# LED_String_QBHP686.net
KiCad netlist of a schematic drawn in Altium Designer
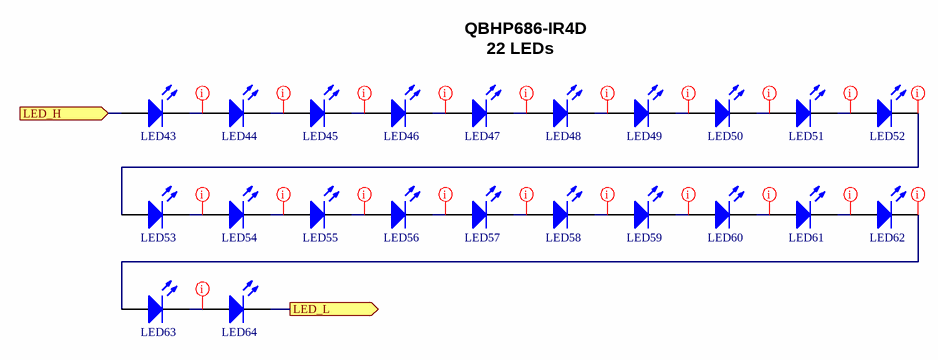
[diagram p0: LED_String_QBHP686.SchDoc]

(export (version "E")
  (design (tool "Eeschema 10.0.6"))
  (components
    (comp (ref "LED43")
      (value "QBHP686-IR4D")
      (footprint "QBHP686-IR4D")
      (description "Infrared (IR) Emitter 740nm 1.8V 100mA 5.6mW/sr @ 50mA 120° 1411 (3528 Metric)")
      (fields (field (name "MFR") "QT Brightek (QTB)") (field (name "MANUFACTURER") "QT-Brightek"))
      (libsource (lib "ETHZ Vault") (part "LED"))
    )
    (comp (ref "LED44")
      (value "QBHP686-IR4D")
      (footprint "QBHP686-IR4D")
      (description "Infrared (IR) Emitter 740nm 1.8V 100mA 5.6mW/sr @ 50mA 120° 1411 (3528 Metric)")
      (fields (field (name "MFR") "QT Brightek (QTB)") (field (name "MANUFACTURER") "QT-Brightek"))
      (libsource (lib "ETHZ Vault") (part "LED"))
    )
    (comp (ref "LED45")
      (value "QBHP686-IR4D")
      (footprint "QBHP686-IR4D")
      (description "Infrared (IR) Emitter 740nm 1.8V 100mA 5.6mW/sr @ 50mA 120° 1411 (3528 Metric)")
      (fields (field (name "MFR") "QT Brightek (QTB)") (field (name "MANUFACTURER") "QT-Brightek"))
      (libsource (lib "ETHZ Vault") (part "LED"))
    )
    (comp (ref "LED46")
      (value "QBHP686-IR4D")
      (footprint "QBHP686-IR4D")
      (description "Infrared (IR) Emitter 740nm 1.8V 100mA 5.6mW/sr @ 50mA 120° 1411 (3528 Metric)")
      (fields (field (name "MFR") "QT Brightek (QTB)") (field (name "MANUFACTURER") "QT-Brightek"))
      (libsource (lib "ETHZ Vault") (part "LED"))
    )
    (comp (ref "LED47")
      (value "QBHP686-IR4D")
      (footprint "QBHP686-IR4D")
      (description "Infrared (IR) Emitter 740nm 1.8V 100mA 5.6mW/sr @ 50mA 120° 1411 (3528 Metric)")
      (fields (field (name "MFR") "QT Brightek (QTB)") (field (name "MANUFACTURER") "QT-Brightek"))
      (libsource (lib "ETHZ Vault") (part "LED"))
    )
    (comp (ref "LED48")
      (value "QBHP686-IR4D")
      (footprint "QBHP686-IR4D")
      (description "Infrared (IR) Emitter 740nm 1.8V 100mA 5.6mW/sr @ 50mA 120° 1411 (3528 Metric)")
      (fields (field (name "MFR") "QT Brightek (QTB)") (field (name "MANUFACTURER") "QT-Brightek"))
      (libsource (lib "ETHZ Vault") (part "LED"))
    )
    (comp (ref "LED49")
      (value "QBHP686-IR4D")
      (footprint "QBHP686-IR4D")
      (description "Infrared (IR) Emitter 740nm 1.8V 100mA 5.6mW/sr @ 50mA 120° 1411 (3528 Metric)")
      (fields (field (name "MFR") "QT Brightek (QTB)") (field (name "MANUFACTURER") "QT-Brightek"))
      (libsource (lib "ETHZ Vault") (part "LED"))
    )
    (comp (ref "LED50")
      (value "QBHP686-IR4D")
      (footprint "QBHP686-IR4D")
      (description "Infrared (IR) Emitter 740nm 1.8V 100mA 5.6mW/sr @ 50mA 120° 1411 (3528 Metric)")
      (fields (field (name "MFR") "QT Brightek (QTB)") (field (name "MANUFACTURER") "QT-Brightek"))
      (libsource (lib "ETHZ Vault") (part "LED"))
    )
    (comp (ref "LED51")
      (value "QBHP686-IR4D")
      (footprint "QBHP686-IR4D")
      (description "Infrared (IR) Emitter 740nm 1.8V 100mA 5.6mW/sr @ 50mA 120° 1411 (3528 Metric)")
      (fields (field (name "MFR") "QT Brightek (QTB)") (field (name "MANUFACTURER") "QT-Brightek"))
      (libsource (lib "ETHZ Vault") (part "LED"))
    )
    (comp (ref "LED52")
      (value "QBHP686-IR4D")
      (footprint "QBHP686-IR4D")
      (description "Infrared (IR) Emitter 740nm 1.8V 100mA 5.6mW/sr @ 50mA 120° 1411 (3528 Metric)")
      (fields (field (name "MFR") "QT Brightek (QTB)") (field (name "MANUFACTURER") "QT-Brightek"))
      (libsource (lib "ETHZ Vault") (part "LED"))
    )
    (comp (ref "LED53")
      (value "QBHP686-IR4D")
      (footprint "QBHP686-IR4D")
      (description "Infrared (IR) Emitter 740nm 1.8V 100mA 5.6mW/sr @ 50mA 120° 1411 (3528 Metric)")
      (fields (field (name "MFR") "QT Brightek (QTB)") (field (name "MANUFACTURER") "QT-Brightek"))
      (libsource (lib "ETHZ Vault") (part "LED"))
    )
    (comp (ref "LED54")
      (value "QBHP686-IR4D")
      (footprint "QBHP686-IR4D")
      (description "Infrared (IR) Emitter 740nm 1.8V 100mA 5.6mW/sr @ 50mA 120° 1411 (3528 Metric)")
      (fields (field (name "MFR") "QT Brightek (QTB)") (field (name "MANUFACTURER") "QT-Brightek"))
      (libsource (lib "ETHZ Vault") (part "LED"))
    )
    (comp (ref "LED55")
      (value "QBHP686-IR4D")
      (footprint "QBHP686-IR4D")
      (description "Infrared (IR) Emitter 740nm 1.8V 100mA 5.6mW/sr @ 50mA 120° 1411 (3528 Metric)")
      (fields (field (name "MFR") "QT Brightek (QTB)") (field (name "MANUFACTURER") "QT-Brightek"))
      (libsource (lib "ETHZ Vault") (part "LED"))
    )
    (comp (ref "LED56")
      (value "QBHP686-IR4D")
      (footprint "QBHP686-IR4D")
      (description "Infrared (IR) Emitter 740nm 1.8V 100mA 5.6mW/sr @ 50mA 120° 1411 (3528 Metric)")
      (fields (field (name "MFR") "QT Brightek (QTB)") (field (name "MANUFACTURER") "QT-Brightek"))
      (libsource (lib "ETHZ Vault") (part "LED"))
    )
    (comp (ref "LED57")
      (value "QBHP686-IR4D")
      (footprint "QBHP686-IR4D")
      (description "Infrared (IR) Emitter 740nm 1.8V 100mA 5.6mW/sr @ 50mA 120° 1411 (3528 Metric)")
      (fields (field (name "MFR") "QT Brightek (QTB)") (field (name "MANUFACTURER") "QT-Brightek"))
      (libsource (lib "ETHZ Vault") (part "LED"))
    )
    (comp (ref "LED58")
      (value "QBHP686-IR4D")
      (footprint "QBHP686-IR4D")
      (description "Infrared (IR) Emitter 740nm 1.8V 100mA 5.6mW/sr @ 50mA 120° 1411 (3528 Metric)")
      (fields (field (name "MFR") "QT Brightek (QTB)") (field (name "MANUFACTURER") "QT-Brightek"))
      (libsource (lib "ETHZ Vault") (part "LED"))
    )
    (comp (ref "LED59")
      (value "QBHP686-IR4D")
      (footprint "QBHP686-IR4D")
      (description "Infrared (IR) Emitter 740nm 1.8V 100mA 5.6mW/sr @ 50mA 120° 1411 (3528 Metric)")
      (fields (field (name "MFR") "QT Brightek (QTB)") (field (name "MANUFACTURER") "QT-Brightek"))
      (libsource (lib "ETHZ Vault") (part "LED"))
    )
    (comp (ref "LED60")
      (value "QBHP686-IR4D")
      (footprint "QBHP686-IR4D")
      (description "Infrared (IR) Emitter 740nm 1.8V 100mA 5.6mW/sr @ 50mA 120° 1411 (3528 Metric)")
      (fields (field (name "MFR") "QT Brightek (QTB)") (field (name "MANUFACTURER") "QT-Brightek"))
      (libsource (lib "ETHZ Vault") (part "LED"))
    )
    (comp (ref "LED61")
      (value "QBHP686-IR4D")
      (footprint "QBHP686-IR4D")
      (description "Infrared (IR) Emitter 740nm 1.8V 100mA 5.6mW/sr @ 50mA 120° 1411 (3528 Metric)")
      (fields (field (name "MFR") "QT Brightek (QTB)") (field (name "MANUFACTURER") "QT-Brightek"))
      (libsource (lib "ETHZ Vault") (part "LED"))
    )
    (comp (ref "LED62")
      (value "QBHP686-IR4D")
      (footprint "QBHP686-IR4D")
      (description "Infrared (IR) Emitter 740nm 1.8V 100mA 5.6mW/sr @ 50mA 120° 1411 (3528 Metric)")
      (fields (field (name "MFR") "QT Brightek (QTB)") (field (name "MANUFACTURER") "QT-Brightek"))
      (libsource (lib "ETHZ Vault") (part "LED"))
    )
    (comp (ref "LED63")
      (value "QBHP686-IR4D")
      (footprint "QBHP686-IR4D")
      (description "Infrared (IR) Emitter 740nm 1.8V 100mA 5.6mW/sr @ 50mA 120° 1411 (3528 Metric)")
      (fields (field (name "MFR") "QT Brightek (QTB)") (field (name "MANUFACTURER") "QT-Brightek"))
      (libsource (lib "ETHZ Vault") (part "LED"))
    )
    (comp (ref "LED64")
      (value "QBHP686-IR4D")
      (footprint "QBHP686-IR4D")
      (description "Infrared (IR) Emitter 740nm 1.8V 100mA 5.6mW/sr @ 50mA 120° 1411 (3528 Metric)")
      (fields (field (name "MFR") "QT Brightek (QTB)") (field (name "MANUFACTURER") "QT-Brightek"))
      (libsource (lib "ETHZ Vault") (part "LED"))
    )
  )
  (nets
    (net (code "1") (name "/LED_H") (class "Default")
      (node (ref "LED43") (pin "2") (pinfunction "A_2") (pintype "passive"))
    )
    (net (code "2") (name "/LED_L") (class "Default")
      (node (ref "LED64") (pin "1") (pinfunction "K_1") (pintype "passive"))
    )
    (net (code "3") (name "Net-(LED43-K)") (class "Default")
      (node (ref "LED43") (pin "1") (pinfunction "K_1") (pintype "passive"))
      (node (ref "LED44") (pin "2") (pinfunction "A_2") (pintype "passive"))
    )
    (net (code "4") (name "Net-(LED44-K)") (class "Default")
      (node (ref "LED44") (pin "1") (pinfunction "K_1") (pintype "passive"))
      (node (ref "LED45") (pin "2") (pinfunction "A_2") (pintype "passive"))
    )
    (net (code "5") (name "Net-(LED45-K)") (class "Default")
      (node (ref "LED45") (pin "1") (pinfunction "K_1") (pintype "passive"))
      (node (ref "LED46") (pin "2") (pinfunction "A_2") (pintype "passive"))
    )
    (net (code "6") (name "Net-(LED46-K)") (class "Default")
      (node (ref "LED46") (pin "1") (pinfunction "K_1") (pintype "passive"))
      (node (ref "LED47") (pin "2") (pinfunction "A_2") (pintype "passive"))
    )
    (net (code "7") (name "Net-(LED47-K)") (class "Default")
      (node (ref "LED47") (pin "1") (pinfunction "K_1") (pintype "passive"))
      (node (ref "LED48") (pin "2") (pinfunction "A_2") (pintype "passive"))
    )
    (net (code "8") (name "Net-(LED48-K)") (class "Default")
      (node (ref "LED48") (pin "1") (pinfunction "K_1") (pintype "passive"))
      (node (ref "LED49") (pin "2") (pinfunction "A_2") (pintype "passive"))
    )
    (net (code "9") (name "Net-(LED49-K)") (class "Default")
      (node (ref "LED49") (pin "1") (pinfunction "K_1") (pintype "passive"))
      (node (ref "LED50") (pin "2") (pinfunction "A_2") (pintype "passive"))
    )
    (net (code "10") (name "Net-(LED50-K)") (class "Default")
      (node (ref "LED50") (pin "1") (pinfunction "K_1") (pintype "passive"))
      (node (ref "LED51") (pin "2") (pinfunction "A_2") (pintype "passive"))
    )
    (net (code "11") (name "Net-(LED51-K)") (class "Default")
      (node (ref "LED51") (pin "1") (pinfunction "K_1") (pintype "passive"))
      (node (ref "LED52") (pin "2") (pinfunction "A_2") (pintype "passive"))
    )
    (net (code "12") (name "Net-(LED52-K)") (class "Default")
      (node (ref "LED52") (pin "1") (pinfunction "K_1") (pintype "passive"))
      (node (ref "LED53") (pin "2") (pinfunction "A_2") (pintype "passive"))
    )
    (net (code "13") (name "Net-(LED53-K)") (class "Default")
      (node (ref "LED53") (pin "1") (pinfunction "K_1") (pintype "passive"))
      (node (ref "LED54") (pin "2") (pinfunction "A_2") (pintype "passive"))
    )
    (net (code "14") (name "Net-(LED54-K)") (class "Default")
      (node (ref "LED54") (pin "1") (pinfunction "K_1") (pintype "passive"))
      (node (ref "LED55") (pin "2") (pinfunction "A_2") (pintype "passive"))
    )
    (net (code "15") (name "Net-(LED55-K)") (class "Default")
      (node (ref "LED55") (pin "1") (pinfunction "K_1") (pintype "passive"))
      (node (ref "LED56") (pin "2") (pinfunction "A_2") (pintype "passive"))
    )
    (net (code "16") (name "Net-(LED56-K)") (class "Default")
      (node (ref "LED56") (pin "1") (pinfunction "K_1") (pintype "passive"))
      (node (ref "LED57") (pin "2") (pinfunction "A_2") (pintype "passive"))
    )
    (net (code "17") (name "Net-(LED57-K)") (class "Default")
      (node (ref "LED57") (pin "1") (pinfunction "K_1") (pintype "passive"))
      (node (ref "LED58") (pin "2") (pinfunction "A_2") (pintype "passive"))
    )
    (net (code "18") (name "Net-(LED58-K)") (class "Default")
      (node (ref "LED58") (pin "1") (pinfunction "K_1") (pintype "passive"))
      (node (ref "LED59") (pin "2") (pinfunction "A_2") (pintype "passive"))
    )
    (net (code "19") (name "Net-(LED59-K)") (class "Default")
      (node (ref "LED59") (pin "1") (pinfunction "K_1") (pintype "passive"))
      (node (ref "LED60") (pin "2") (pinfunction "A_2") (pintype "passive"))
    )
    (net (code "20") (name "Net-(LED60-K)") (class "Default")
      (node (ref "LED60") (pin "1") (pinfunction "K_1") (pintype "passive"))
      (node (ref "LED61") (pin "2") (pinfunction "A_2") (pintype "passive"))
    )
    (net (code "21") (name "Net-(LED61-K)") (class "Default")
      (node (ref "LED61") (pin "1") (pinfunction "K_1") (pintype "passive"))
      (node (ref "LED62") (pin "2") (pinfunction "A_2") (pintype "passive"))
    )
    (net (code "22") (name "Net-(LED62-K)") (class "Default")
      (node (ref "LED62") (pin "1") (pinfunction "K_1") (pintype "passive"))
      (node (ref "LED63") (pin "2") (pinfunction "A_2") (pintype "passive"))
    )
    (net (code "23") (name "Net-(LED63-K)") (class "Default")
      (node (ref "LED63") (pin "1") (pinfunction "K_1") (pintype "passive"))
      (node (ref "LED64") (pin "2") (pinfunction "A_2") (pintype "passive"))
    )
  )
)
